# MP257_14x14.net
KiCad netlist of a schematic drawn in Altium Designer
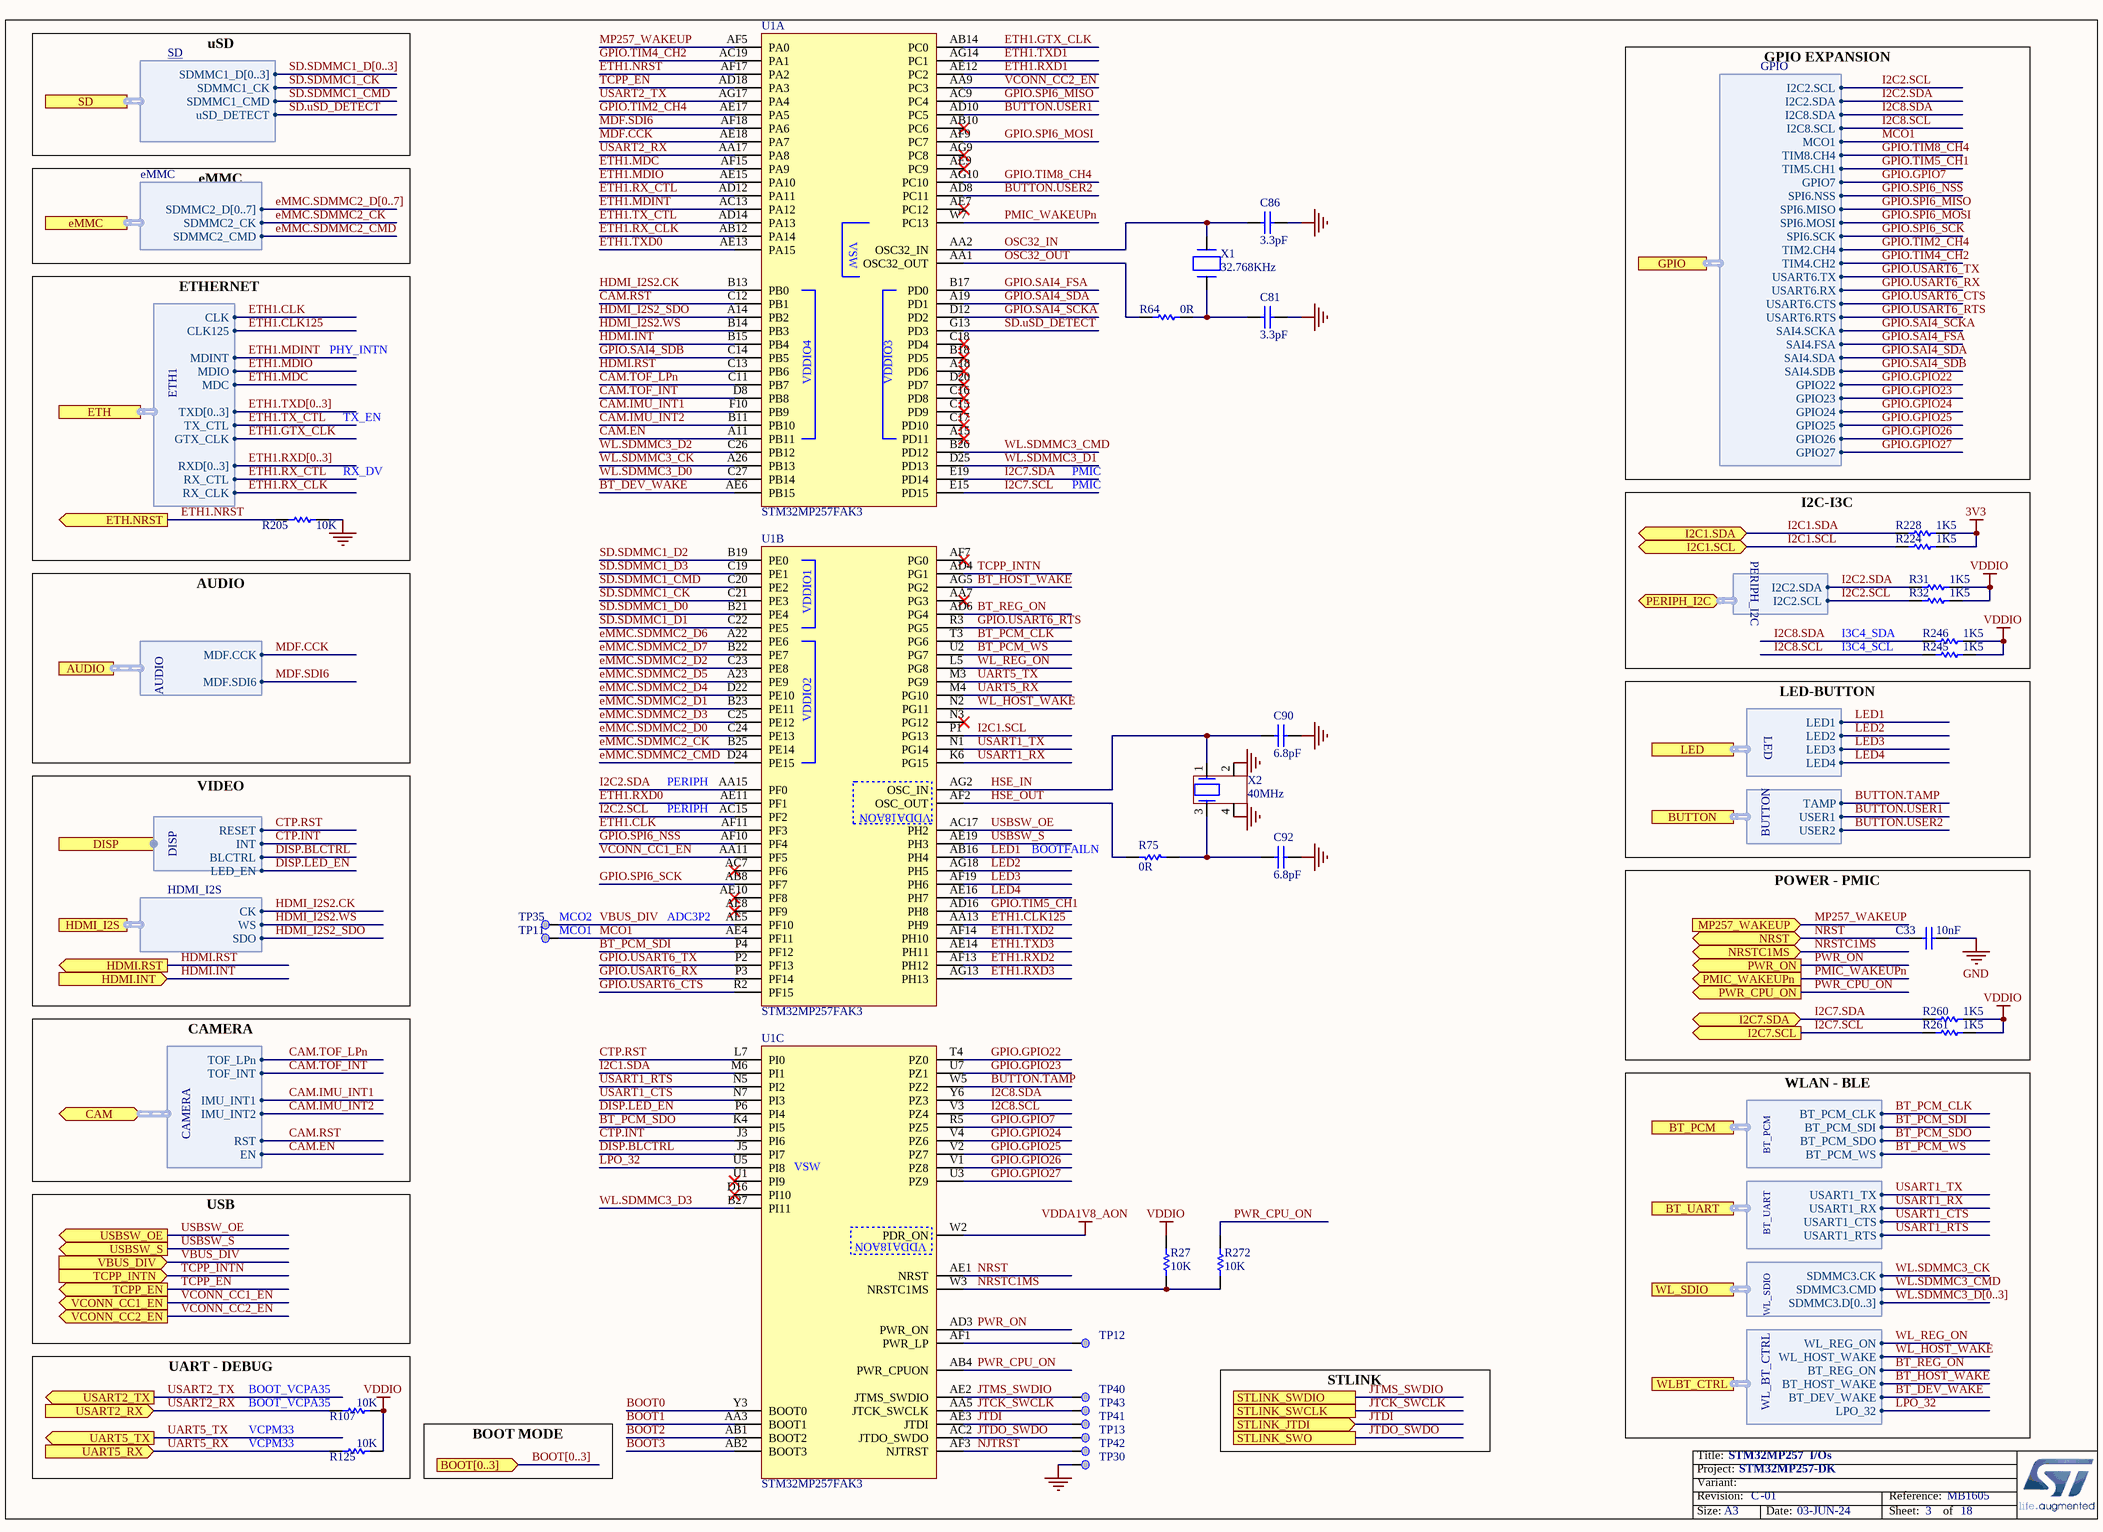
[diagram p0: MP257_14x14.SchDoc]

(export (version "E")
  (design (tool "Eeschema 10.0.6"))
  (components
    (comp (ref "C33")
      (value "10nF")
      (footprint "C0402")
      (description "Capacitor, MLCC, 10nF, 16V, X7R, 10%, 0402, T=0.5mm")
      (fields
        (field (name "INTERNAL_PART_NUMBER") "MCD-00011")
        (field (name "MANUFACTURER_PART_NUMBER") "CC0402KRX7R7BB103")
        (field (name "PROVIDED_BY") "SUBCO")
      )
      (libsource (lib "MCD_PARTS_database") (part "Capacitor"))
    )
    (comp (ref "C81")
      (value "3.3pF")
      (footprint "C0402")
      (description "Capacitor, MLCC, 3.3pF, 50V, NPO, +/-0.1pF, 0402, T=0.5mm")
      (fields (field (name "INTERNAL_PART_NUMBER") "MCD-01775") (field (name "MANUFACTURER") "YAGEO"))
      (libsource (lib "MCD_PARTS_database") (part "Capacitor"))
    )
    (comp (ref "C86")
      (value "3.3pF")
      (footprint "C0402")
      (description "Capacitor, MLCC, 3.3pF, 50V, NPO, +/-0.1pF, 0402, T=0.5mm")
      (fields (field (name "INTERNAL_PART_NUMBER") "MCD-01775") (field (name "MANUFACTURER") "YAGEO"))
      (libsource (lib "MCD_PARTS_database") (part "Capacitor"))
    )
    (comp (ref "C90")
      (value "6.8pF")
      (footprint "C0402")
      (description "Capacitor, MLCC, 6.8pF, 50V, NPO, +-0.25pF, 0402, T=0.5mm")
      (fields
        (field (name "INTERNAL_PART_NUMBER") "MCD-00674")
        (field (name "MANUFACTURER_PART_NUMBER") "CC0402CRNPO9BN6R8")
        (field (name "PROVIDED_BY") "SUBCO")
      )
      (libsource (lib "MCD_PARTS_database") (part "Capacitor"))
    )
    (comp (ref "C92")
      (value "6.8pF")
      (footprint "C0402")
      (description "Capacitor, MLCC, 6.8pF, 50V, NPO, +-0.25pF, 0402, T=0.5mm")
      (fields
        (field (name "INTERNAL_PART_NUMBER") "MCD-00674")
        (field (name "MANUFACTURER_PART_NUMBER") "CC0402CRNPO9BN6R8")
        (field (name "PROVIDED_BY") "SUBCO")
      )
      (libsource (lib "MCD_PARTS_database") (part "Capacitor"))
    )
    (comp (ref "R27")
      (value "10K")
      (footprint "R0402")
      (description "Resistor,10K,0402,1%,1/16W")
      (fields (field (name "INTERNAL_PART_NUMBER") "MCD-00053") (field (name "BMS_PART_NUMBER") "9131590"))
      (libsource (lib "MCD_PARTS_database") (part "Resistor"))
    )
    (comp (ref "R31")
      (value "1K5")
      (footprint "R0402")
      (description "Resistor,1K5,0402,1%,1/16W")
      (fields (field (name "INTERNAL_PART_NUMBER") "MCD-00068") (field (name "MANUFACTURER") "YAGEO"))
      (libsource (lib "MCD_PARTS_database") (part "Resistor"))
    )
    (comp (ref "R32")
      (value "1K5")
      (footprint "R0402")
      (description "Resistor,1K5,0402,1%,1/16W")
      (fields (field (name "INTERNAL_PART_NUMBER") "MCD-00068") (field (name "MANUFACTURER") "YAGEO"))
      (libsource (lib "MCD_PARTS_database") (part "Resistor"))
    )
    (comp (ref "R64")
      (value "0R")
      (footprint "R0402")
      (description "Resistor,0R,0402,5%,1/16W")
      (fields
        (field (name "INTERNAL_PART_NUMBER") "MCD-00052")
        (field (name "MANUFACTURER_PART_NUMBER") "RC0402JR-070RL")
        (field (name "PROVIDED_BY") "SUBCO")
      )
      (libsource (lib "MCD_PARTS_database") (part "Resistor"))
    )
    (comp (ref "R75")
      (value "0R")
      (footprint "R0402")
      (description "Resistor,0R,0402,5%,1/16W")
      (fields
        (field (name "INTERNAL_PART_NUMBER") "MCD-00052")
        (field (name "MANUFACTURER_PART_NUMBER") "RC0402JR-070RL")
        (field (name "PROVIDED_BY") "SUBCO")
      )
      (libsource (lib "MCD_PARTS_database") (part "Resistor"))
    )
    (comp (ref "R107")
      (value "10K")
      (footprint "R0402")
      (description "Resistor,10K,0402,1%,1/16W")
      (fields (field (name "INTERNAL_PART_NUMBER") "MCD-00053") (field (name "BMS_PART_NUMBER") "9131590"))
      (libsource (lib "MCD_PARTS_database") (part "Resistor"))
    )
    (comp (ref "R125")
      (value "10K")
      (footprint "R0402")
      (description "Resistor,10K,0402,1%,1/16W")
      (fields (field (name "INTERNAL_PART_NUMBER") "MCD-00053") (field (name "BMS_PART_NUMBER") "9131590"))
      (libsource (lib "MCD_PARTS_database") (part "Resistor"))
    )
    (comp (ref "R205")
      (value "10K")
      (footprint "R0402")
      (description "Resistor,10K,0402,1%,1/16W")
      (fields
        (field (name "INTERNAL_PART_NUMBER") "MCD-00053")
        (field (name "MANUFACTURER_PART_NUMBER") "RC0402FR-0710KL")
      )
      (libsource (lib "MCD_PARTS_database") (part "Resistor"))
    )
    (comp (ref "R224")
      (value "1K5")
      (footprint "R0402")
      (description "Resistor,1K5,0402,1%,1/16W")
      (fields (field (name "INTERNAL_PART_NUMBER") "MCD-00068") (field (name "MANUFACTURER") "YAGEO"))
      (libsource (lib "MCD_PARTS_database") (part "Resistor"))
    )
    (comp (ref "R228")
      (value "1K5")
      (footprint "R0402")
      (description "Resistor,1K5,0402,1%,1/16W")
      (fields (field (name "INTERNAL_PART_NUMBER") "MCD-00068") (field (name "MANUFACTURER") "YAGEO"))
      (libsource (lib "MCD_PARTS_database") (part "Resistor"))
    )
    (comp (ref "R245")
      (value "1K5")
      (footprint "R0402")
      (description "Resistor,1K5,0402,1%,1/16W")
      (fields (field (name "INTERNAL_PART_NUMBER") "MCD-00068") (field (name "MANUFACTURER") "YAGEO"))
      (libsource (lib "MCD_PARTS_database") (part "Resistor"))
    )
    (comp (ref "R246")
      (value "1K5")
      (footprint "R0402")
      (description "Resistor,1K5,0402,1%,1/16W")
      (fields (field (name "INTERNAL_PART_NUMBER") "MCD-00068") (field (name "MANUFACTURER") "YAGEO"))
      (libsource (lib "MCD_PARTS_database") (part "Resistor"))
    )
    (comp (ref "R260")
      (value "1K5")
      (footprint "R0402")
      (description "Resistor,1K5,0402,1%,1/16W")
      (fields (field (name "INTERNAL_PART_NUMBER") "MCD-00068") (field (name "MANUFACTURER") "YAGEO"))
      (libsource (lib "MCD_PARTS_database") (part "Resistor"))
    )
    (comp (ref "R261")
      (value "1K5")
      (footprint "R0402")
      (description "Resistor,1K5,0402,1%,1/16W")
      (fields (field (name "INTERNAL_PART_NUMBER") "MCD-00068") (field (name "MANUFACTURER") "YAGEO"))
      (libsource (lib "MCD_PARTS_database") (part "Resistor"))
    )
    (comp (ref "R272")
      (value "10K")
      (footprint "R0402")
      (description "Resistor,10K,0402,1%,1/16W")
      (fields (field (name "INTERNAL_PART_NUMBER") "MCD-00053") (field (name "BMS_PART_NUMBER") "9131590"))
      (libsource (lib "MCD_PARTS_database") (part "Resistor"))
    )
    (comp (ref "TP11")
      (value "Test Point")
      (footprint "TP_SMD_1MM")
      (description "Test Point 1mm")
      (fields
        (field (name "INTERNAL_PART_NUMBER") "MCD-00074")
        (field (name "MANUFACTURER_PART_NUMBER") "n/a")
      )
      (libsource (lib "") (part "Test Point_1"))
    )
    (comp (ref "TP12")
      (value "Test Point")
      (footprint "TP_SMD_1MM")
      (description "Test Point 1mm")
      (fields
        (field (name "INTERNAL_PART_NUMBER") "MCD-00074")
        (field (name "MANUFACTURER_PART_NUMBER") "n/a")
      )
      (libsource (lib "MCD_PARTS_database") (part "Test Point"))
    )
    (comp (ref "TP13")
      (value "Test Point")
      (footprint "TP_SMD_1MM")
      (description "Test Point 1mm")
      (fields
        (field (name "INTERNAL_PART_NUMBER") "MCD-00074")
        (field (name "MANUFACTURER_PART_NUMBER") "n/a")
      )
      (libsource (lib "MCD_PARTS_database") (part "Test Point"))
    )
    (comp (ref "TP30")
      (value "Test Point")
      (footprint "TP_SMD_1MM")
      (description "Test Point 1mm")
      (fields
        (field (name "INTERNAL_PART_NUMBER") "MCD-00074")
        (field (name "MANUFACTURER_PART_NUMBER") "n/a")
      )
      (libsource (lib "MCD_PARTS_database") (part "Test Point"))
    )
    (comp (ref "TP35")
      (value "Test Point")
      (footprint "TP_SMD_1MM")
      (description "Test Point 1mm")
      (fields
        (field (name "INTERNAL_PART_NUMBER") "MCD-00074")
        (field (name "MANUFACTURER_PART_NUMBER") "n/a")
      )
      (libsource (lib "") (part "Test Point_1"))
    )
    (comp (ref "TP40")
      (value "Test Point")
      (footprint "TP_SMD_1MM")
      (description "Test Point 1mm")
      (fields
        (field (name "INTERNAL_PART_NUMBER") "MCD-00074")
        (field (name "MANUFACTURER_PART_NUMBER") "n/a")
      )
      (libsource (lib "MCD_PARTS_database") (part "Test Point"))
    )
    (comp (ref "TP41")
      (value "Test Point")
      (footprint "TP_SMD_1MM")
      (description "Test Point 1mm")
      (fields
        (field (name "INTERNAL_PART_NUMBER") "MCD-00074")
        (field (name "MANUFACTURER_PART_NUMBER") "n/a")
      )
      (libsource (lib "MCD_PARTS_database") (part "Test Point"))
    )
    (comp (ref "TP42")
      (value "Test Point")
      (footprint "TP_SMD_1MM")
      (description "Test Point 1mm")
      (fields
        (field (name "INTERNAL_PART_NUMBER") "MCD-00074")
        (field (name "MANUFACTURER_PART_NUMBER") "n/a")
      )
      (libsource (lib "MCD_PARTS_database") (part "Test Point"))
    )
    (comp (ref "TP43")
      (value "Test Point")
      (footprint "TP_SMD_1MM")
      (description "Test Point 1mm")
      (fields
        (field (name "INTERNAL_PART_NUMBER") "MCD-00074")
        (field (name "MANUFACTURER_PART_NUMBER") "n/a")
      )
      (libsource (lib "MCD_PARTS_database") (part "Test Point"))
    )
    (comp (ref "U1")
      (value "STM32MP257FAK3")
      (footprint "ICC_TFBGA424_14X14_P050_H1P20_CODE-B0A2")
      (description "MPU , 2xCortex-A35@1.5GHz, Cortex-M33@400MHz, TFBGA 14x14, pitch 0.5, 648KB SRAM, With Crypto")
      (fields
        (field (name "INTERNAL_PART_NUMBER") "MCD-03375")
        (field (name "MANUFACTURER") "STMICROELECTRONICS")
      )
      (libsource (lib "MCD_PARTS_database") (part "STM32MP257FAK3"))
    )
    (comp (ref "X1")
      (value "32.768KHz")
      (footprint "CRY_NX2012SA_2P")
      (description "Crystal, 32.768kHz, 6pF, +/-20ppm, 80K, 2.05x1.2mm")
      (fields (field (name "INTERNAL_PART_NUMBER") "MCD-01479") (field (name "BMS_PART_NUMBER") "9157049"))
      (libsource (lib "MCD_PARTS_database") (part "XTAL_2_PINS"))
    )
    (comp (ref "X2")
      (value "40MHz")
      (footprint "CRY_NX1612SA_4P")
      (description "Crystal, 40MHz, 6pF, +/-20ppm, 80R, 1.6x1.2mm")
      (fields (field (name "INTERNAL_PART_NUMBER") "MCD-02344") (field (name "MANUFACTURER") "NDK"))
      (libsource (lib "MCD_PARTS_database") (part "XTAL_4_PINS"))
    )
  )
  (nets
    (net (code "17") (name "/BOOT0") (class "Default")
      (node (ref "U1") (pin "Y3") (pinfunction "BOOT0_Y3") (pintype "passive"))
    )
    (net (code "18") (name "/BOOT1") (class "Default")
      (node (ref "U1") (pin "AA3") (pinfunction "BOOT1_AA3") (pintype "passive"))
    )
    (net (code "19") (name "/BOOT2") (class "Default")
      (node (ref "U1") (pin "AB1") (pinfunction "BOOT2_AB1") (pintype "passive"))
    )
    (net (code "20") (name "/BOOT3") (class "Default")
      (node (ref "U1") (pin "AB2") (pinfunction "BOOT3_AB2") (pintype "passive"))
    )
    (net (code "22") (name "/BT_DEV_WAKE") (class "Default")
      (node (ref "U1") (pin "AE6") (pinfunction "PB15_AE6") (pintype "passive"))
    )
    (net (code "23") (name "/BT_HOST_WAKE") (class "Default")
      (node (ref "U1") (pin "AG5") (pinfunction "PG2_AG5") (pintype "passive"))
    )
    (net (code "24") (name "/BT_PCM_CLK") (class "Default")
      (node (ref "U1") (pin "T3") (pinfunction "PG6_T3") (pintype "passive"))
    )
    (net (code "25") (name "/BT_PCM_SDI") (class "Default")
      (node (ref "U1") (pin "P4") (pinfunction "PF12_P4") (pintype "passive"))
    )
    (net (code "26") (name "/BT_PCM_SDO") (class "Default")
      (node (ref "U1") (pin "K4") (pinfunction "PI5_K4") (pintype "passive"))
    )
    (net (code "27") (name "/BT_PCM_WS") (class "Default")
      (node (ref "U1") (pin "U2") (pinfunction "PG7_U2") (pintype "passive"))
    )
    (net (code "28") (name "/BT_REG_ON") (class "Default")
      (node (ref "U1") (pin "AD6") (pinfunction "PG4_AD6") (pintype "passive"))
    )
    (net (code "29") (name "/BUTTON.TAMP") (class "Default")
      (node (ref "U1") (pin "W5") (pinfunction "PZ2_W5") (pintype "passive"))
    )
    (net (code "30") (name "/BUTTON.USER1") (class "Default")
      (node (ref "U1") (pin "AD10") (pinfunction "PC5_AD10") (pintype "passive"))
    )
    (net (code "31") (name "/BUTTON.USER2") (class "Default")
      (node (ref "U1") (pin "AD8") (pinfunction "PC11_AD8") (pintype "passive"))
    )
    (net (code "32") (name "/CAM.EN") (class "Default")
      (node (ref "U1") (pin "A11") (pinfunction "PB11_A11") (pintype "passive"))
    )
    (net (code "33") (name "/CAM.IMU_INT1") (class "Default")
      (node (ref "U1") (pin "F10") (pinfunction "PB9_F10") (pintype "passive"))
    )
    (net (code "34") (name "/CAM.IMU_INT2") (class "Default")
      (node (ref "U1") (pin "B11") (pinfunction "PB10_B11") (pintype "passive"))
    )
    (net (code "35") (name "/CAM.RST") (class "Default")
      (node (ref "U1") (pin "C12") (pinfunction "PB1_C12") (pintype "passive"))
    )
    (net (code "36") (name "/CAM.TOF_INT") (class "Default")
      (node (ref "U1") (pin "D8") (pinfunction "PB8_D8") (pintype "passive"))
    )
    (net (code "37") (name "/CAM.TOF_LPn") (class "Default")
      (node (ref "U1") (pin "C11") (pinfunction "PB7_C11") (pintype "passive"))
    )
    (net (code "38") (name "/CTP.INT") (class "Default")
      (node (ref "U1") (pin "J3") (pinfunction "PI6_J3") (pintype "passive"))
    )
    (net (code "39") (name "/CTP.RST") (class "Default")
      (node (ref "U1") (pin "L7") (pinfunction "PI0_L7") (pintype "passive"))
    )
    (net (code "40") (name "/DISP.BLCTRL") (class "Default")
      (node (ref "U1") (pin "J5") (pinfunction "PI7_J5") (pintype "passive"))
    )
    (net (code "41") (name "/DISP.LED_EN") (class "Default")
      (node (ref "U1") (pin "P6") (pinfunction "PI4_P6") (pintype "passive"))
    )
    (net (code "42") (name "/ETH1.CLK") (class "Default")
      (node (ref "U1") (pin "AF11") (pinfunction "PF3_AF11") (pintype "passive"))
    )
    (net (code "43") (name "/ETH1.CLK125") (class "Default")
      (node (ref "U1") (pin "AA13") (pinfunction "PH9_AA13") (pintype "passive"))
    )
    (net (code "44") (name "/ETH1.GTX_CLK") (class "Default")
      (node (ref "U1") (pin "AB14") (pinfunction "PC0_AB14") (pintype "passive"))
    )
    (net (code "45") (name "/ETH1.MDC") (class "Default")
      (node (ref "U1") (pin "AF15") (pinfunction "PA9_AF15") (pintype "passive"))
    )
    (net (code "46") (name "/ETH1.MDINT") (class "Default")
      (node (ref "U1") (pin "AC13") (pinfunction "PA12_AC13") (pintype "passive"))
    )
    (net (code "47") (name "/ETH1.MDIO") (class "Default")
      (node (ref "U1") (pin "AE15") (pinfunction "PA10_AE15") (pintype "passive"))
    )
    (net (code "48") (name "/ETH1.NRST") (class "Default")
      (node (ref "R205") (pin "1") (pinfunction "1_1") (pintype "passive"))
      (node (ref "U1") (pin "AF17") (pinfunction "PA2_AF17") (pintype "passive"))
    )
    (net (code "49") (name "/ETH1.RXD0") (class "Default")
      (node (ref "U1") (pin "AE11") (pinfunction "PF1_AE11") (pintype "passive"))
    )
    (net (code "50") (name "/ETH1.RXD1") (class "Default")
      (node (ref "U1") (pin "AE12") (pinfunction "PC2_AE12") (pintype "passive"))
    )
    (net (code "51") (name "/ETH1.RXD2") (class "Default")
      (node (ref "U1") (pin "AF13") (pinfunction "PH12_AF13") (pintype "passive"))
    )
    (net (code "52") (name "/ETH1.RXD3") (class "Default")
      (node (ref "U1") (pin "AG13") (pinfunction "PH13_AG13") (pintype "passive"))
    )
    (net (code "54") (name "/ETH1.RX_CLK") (class "Default")
      (node (ref "U1") (pin "AB12") (pinfunction "PA14_AB12") (pintype "passive"))
    )
    (net (code "55") (name "/ETH1.RX_CTL") (class "Default")
      (node (ref "U1") (pin "AD12") (pinfunction "PA11_AD12") (pintype "passive"))
    )
    (net (code "56") (name "/ETH1.TXD0") (class "Default")
      (node (ref "U1") (pin "AE13") (pinfunction "PA15_AE13") (pintype "passive"))
    )
    (net (code "57") (name "/ETH1.TXD1") (class "Default")
      (node (ref "U1") (pin "AG14") (pinfunction "PC1_AG14") (pintype "passive"))
    )
    (net (code "58") (name "/ETH1.TXD2") (class "Default")
      (node (ref "U1") (pin "AF14") (pinfunction "PH10_AF14") (pintype "passive"))
    )
    (net (code "59") (name "/ETH1.TXD3") (class "Default")
      (node (ref "U1") (pin "AE14") (pinfunction "PH11_AE14") (pintype "passive"))
    )
    (net (code "61") (name "/ETH1.TX_CTL") (class "Default")
      (node (ref "U1") (pin "AD14") (pinfunction "PA13_AD14") (pintype "passive"))
    )
    (net (code "62") (name "/GPIO.GPIO7") (class "Default")
      (node (ref "U1") (pin "R5") (pinfunction "PZ5_R5") (pintype "passive"))
    )
    (net (code "63") (name "/GPIO.GPIO22") (class "Default")
      (node (ref "U1") (pin "T4") (pinfunction "PZ0_T4") (pintype "passive"))
    )
    (net (code "64") (name "/GPIO.GPIO23") (class "Default")
      (node (ref "U1") (pin "U7") (pinfunction "PZ1_U7") (pintype "passive"))
    )
    (net (code "65") (name "/GPIO.GPIO24") (class "Default")
      (node (ref "U1") (pin "V4") (pinfunction "PZ6_V4") (pintype "passive"))
    )
    (net (code "66") (name "/GPIO.GPIO25") (class "Default")
      (node (ref "U1") (pin "V2") (pinfunction "PZ7_V2") (pintype "passive"))
    )
    (net (code "67") (name "/GPIO.GPIO26") (class "Default")
      (node (ref "U1") (pin "V1") (pinfunction "PZ8_V1") (pintype "passive"))
    )
    (net (code "68") (name "/GPIO.GPIO27") (class "Default")
      (node (ref "U1") (pin "U3") (pinfunction "PZ9_U3") (pintype "passive"))
    )
    (net (code "69") (name "/GPIO.SAI4_FSA") (class "Default")
      (node (ref "U1") (pin "B17") (pinfunction "PD0_B17") (pintype "passive"))
    )
    (net (code "70") (name "/GPIO.SAI4_SCKA") (class "Default")
      (node (ref "U1") (pin "D12") (pinfunction "PD2_D12") (pintype "passive"))
    )
    (net (code "71") (name "/GPIO.SAI4_SDA") (class "Default")
      (node (ref "U1") (pin "A19") (pinfunction "PD1_A19") (pintype "passive"))
    )
    (net (code "72") (name "/GPIO.SAI4_SDB") (class "Default")
      (node (ref "U1") (pin "C14") (pinfunction "PB5_C14") (pintype "passive"))
    )
    (net (code "73") (name "/GPIO.SPI6_MISO") (class "Default")
      (node (ref "U1") (pin "AC9") (pinfunction "PC4_AC9") (pintype "passive"))
    )
    (net (code "74") (name "/GPIO.SPI6_MOSI") (class "Default")
      (node (ref "U1") (pin "AF9") (pinfunction "PC7_AF9") (pintype "passive"))
    )
    (net (code "75") (name "/GPIO.SPI6_NSS") (class "Default")
      (node (ref "U1") (pin "AF10") (pinfunction "PF4_AF10") (pintype "passive"))
    )
    (net (code "76") (name "/GPIO.SPI6_SCK") (class "Default")
      (node (ref "U1") (pin "AB8") (pinfunction "PF7_AB8") (pintype "passive"))
    )
    (net (code "77") (name "/GPIO.TIM2_CH4") (class "Default")
      (node (ref "U1") (pin "AE17") (pinfunction "PA5_AE17") (pintype "passive"))
    )
    (net (code "78") (name "/GPIO.TIM4_CH2") (class "Default")
      (node (ref "U1") (pin "AC19") (pinfunction "PA1_AC19") (pintype "passive"))
    )
    (net (code "79") (name "/GPIO.TIM5_CH1") (class "Default")
      (node (ref "U1") (pin "AD16") (pinfunction "PH8_AD16") (pintype "passive"))
    )
    (net (code "80") (name "/GPIO.TIM8_CH4") (class "Default")
      (node (ref "U1") (pin "AG10") (pinfunction "PC10_AG10") (pintype "passive"))
    )
    (net (code "81") (name "/GPIO.USART6_CTS") (class "Default")
      (node (ref "U1") (pin "R2") (pinfunction "PF15_R2") (pintype "passive"))
    )
    (net (code "82") (name "/GPIO.USART6_RTS") (class "Default")
      (node (ref "U1") (pin "R3") (pinfunction "PG5_R3") (pintype "passive"))
    )
    (net (code "83") (name "/GPIO.USART6_RX") (class "Default")
      (node (ref "U1") (pin "P3") (pinfunction "PF14_P3") (pintype "passive"))
    )
    (net (code "84") (name "/GPIO.USART6_TX") (class "Default")
      (node (ref "U1") (pin "P2") (pinfunction "PF13_P2") (pintype "passive"))
    )
    (net (code "85") (name "/HDMI.INT") (class "Default")
      (node (ref "U1") (pin "B15") (pinfunction "PB4_B15") (pintype "passive"))
    )
    (net (code "86") (name "/HDMI.RST") (class "Default")
      (node (ref "U1") (pin "C13") (pinfunction "PB6_C13") (pintype "passive"))
    )
    (net (code "87") (name "/HDMI_I2S2.CK") (class "Default")
      (node (ref "U1") (pin "B13") (pinfunction "PB0_B13") (pintype "passive"))
    )
    (net (code "88") (name "/HDMI_I2S2.WS") (class "Default")
      (node (ref "U1") (pin "B14") (pinfunction "PB3_B14") (pintype "passive"))
    )
    (net (code "89") (name "/HDMI_I2S2_SDO") (class "Default")
      (node (ref "U1") (pin "A14") (pinfunction "PB2_A14") (pintype "passive"))
    )
    (net (code "90") (name "/HSE_IN") (class "Default")
      (node (ref "C90") (pin "2") (pinfunction "2_2") (pintype "passive"))
      (node (ref "U1") (pin "AG2") (pinfunction "OSC_IN_AG2") (pintype "passive"))
      (node (ref "X2") (pin "1") (pinfunction "1_1") (pintype "passive"))
    )
    (net (code "91") (name "/HSE_OUT") (class "Default")
      (node (ref "R75") (pin "2") (pinfunction "2_2") (pintype "passive"))
      (node (ref "U1") (pin "AF2") (pinfunction "OSC_OUT_AF2") (pintype "passive"))
    )
    (net (code "92") (name "/I2C1.SCL") (class "Default")
      (node (ref "R224") (pin "1") (pinfunction "1_1") (pintype "passive"))
      (node (ref "U1") (pin "P1") (pinfunction "PG13_P1") (pintype "passive"))
    )
    (net (code "93") (name "/I2C1.SDA") (class "Default")
      (node (ref "R228") (pin "1") (pinfunction "1_1") (pintype "passive"))
      (node (ref "U1") (pin "M6") (pinfunction "PI1_M6") (pintype "passive"))
    )
    (net (code "94") (name "/I2C2.SCL") (class "Default")
      (node (ref "R32") (pin "1") (pinfunction "1_1") (pintype "passive"))
      (node (ref "U1") (pin "AC15") (pinfunction "PF2_AC15") (pintype "passive"))
    )
    (net (code "95") (name "/I2C2.SDA") (class "Default")
      (node (ref "R31") (pin "1") (pinfunction "1_1") (pintype "passive"))
      (node (ref "U1") (pin "AA15") (pinfunction "PF0_AA15") (pintype "passive"))
    )
    (net (code "96") (name "/I2C7.SCL") (class "Default")
      (node (ref "R261") (pin "1") (pinfunction "1_1") (pintype "passive"))
      (node (ref "U1") (pin "E15") (pinfunction "PD15_E15") (pintype "passive"))
    )
    (net (code "97") (name "/I2C7.SDA") (class "Default")
      (node (ref "R260") (pin "1") (pinfunction "1_1") (pintype "passive"))
      (node (ref "U1") (pin "E19") (pinfunction "PD14_E19") (pintype "passive"))
    )
    (net (code "98") (name "/I2C8.SCL") (class "Default")
      (node (ref "R245") (pin "1") (pinfunction "1_1") (pintype "passive"))
      (node (ref "U1") (pin "V3") (pinfunction "PZ4_V3") (pintype "passive"))
    )
    (net (code "99") (name "/I2C8.SDA") (class "Default")
      (node (ref "R246") (pin "1") (pinfunction "1_1") (pintype "passive"))
      (node (ref "U1") (pin "Y6") (pinfunction "PZ3_Y6") (pintype "passive"))
    )
    (net (code "100") (name "/JTCK_SWCLK") (class "Default")
      (node (ref "TP43") (pin "1") (pinfunction "1_1") (pintype "passive"))
      (node (ref "U1") (pin "AA5") (pinfunction "JTCK_SWCLK_AA5") (pintype "passive"))
    )
    (net (code "101") (name "/JTDI") (class "Default")
      (node (ref "TP41") (pin "1") (pinfunction "1_1") (pintype "passive"))
      (node (ref "U1") (pin "AE3") (pinfunction "JTDI_AE3") (pintype "passive"))
    )
    (net (code "102") (name "/JTDO_SWDO") (class "Default")
      (node (ref "TP13") (pin "1") (pinfunction "1_1") (pintype "passive"))
      (node (ref "U1") (pin "AC2") (pinfunction "JTDO_SWDO_AC2") (pintype "passive"))
    )
    (net (code "103") (name "/JTMS_SWDIO") (class "Default")
      (node (ref "TP40") (pin "1") (pinfunction "1_1") (pintype "passive"))
      (node (ref "U1") (pin "AE2") (pinfunction "JTMS_SWDIO_AE2") (pintype "passive"))
    )
    (net (code "104") (name "/LED1") (class "Default")
      (node (ref "U1") (pin "AB16") (pinfunction "PH4_AB16") (pintype "passive"))
    )
    (net (code "105") (name "/LED2") (class "Default")
      (node (ref "U1") (pin "AG18") (pinfunction "PH5_AG18") (pintype "passive"))
    )
    (net (code "106") (name "/LED3") (class "Default")
      (node (ref "U1") (pin "AF19") (pinfunction "PH6_AF19") (pintype "passive"))
    )
    (net (code "107") (name "/LED4") (class "Default")
      (node (ref "U1") (pin "AE16") (pinfunction "PH7_AE16") (pintype "passive"))
    )
    (net (code "108") (name "/LPO_32") (class "Default")
      (node (ref "U1") (pin "U5") (pinfunction "PI8_U5") (pintype "passive"))
    )
    (net (code "109") (name "/MCO1") (class "Default")
      (node (ref "TP11") (pin "1") (pinfunction "1_1") (pintype "passive"))
      (node (ref "U1") (pin "AE4") (pinfunction "PF11_AE4") (pintype "passive"))
    )
    (net (code "110") (name "/MDF.CCK") (class "Default")
      (node (ref "U1") (pin "AE18") (pinfunction "PA7_AE18") (pintype "passive"))
    )
    (net (code "111") (name "/MDF.SDI6") (class "Default")
      (node (ref "U1") (pin "AF18") (pinfunction "PA6_AF18") (pintype "passive"))
    )
    (net (code "112") (name "/MP257_WAKEUP") (class "Default")
      (node (ref "U1") (pin "AF5") (pinfunction "PA0_AF5") (pintype "passive"))
    )
    (net (code "113") (name "/NJTRST") (class "Default")
      (node (ref "TP42") (pin "1") (pinfunction "1_1") (pintype "passive"))
      (node (ref "U1") (pin "AF3") (pinfunction "NJTRST_AF3") (pintype "passive"))
    )
    (net (code "114") (name "/NRST") (class "Default")
      (node (ref "C33") (pin "2") (pinfunction "2_2") (pintype "passive"))
      (node (ref "U1") (pin "AE1") (pinfunction "NRST_AE1") (pintype "passive"))
    )
    (net (code "115") (name "/NRSTC1MS") (class "Default")
      (node (ref "R27") (pin "1") (pinfunction "1_1") (pintype "passive"))
      (node (ref "R272") (pin "1") (pinfunction "1_1") (pintype "passive"))
      (node (ref "U1") (pin "W3") (pinfunction "NRSTC1MS_W3") (pintype "passive"))
    )
    (net (code "116") (name "/OSC32_IN") (class "Default")
      (node (ref "C86") (pin "1") (pinfunction "1_1") (pintype "passive"))
      (node (ref "U1") (pin "AA2") (pinfunction "OSC32_IN_AA2") (pintype "passive"))
      (node (ref "X1") (pin "2") (pinfunction "X2_2") (pintype "passive"))
    )
    (net (code "117") (name "/OSC32_OUT") (class "Default")
      (node (ref "R64") (pin "1") (pinfunction "1_1") (pintype "passive"))
      (node (ref "U1") (pin "AA1") (pinfunction "OSC32_OUT_AA1") (pintype "passive"))
    )
    (net (code "118") (name "/PMIC_WAKEUPn") (class "Default")
      (node (ref "U1") (pin "W7") (pinfunction "PC13_W7") (pintype "passive"))
    )
    (net (code "119") (name "/PWR_CPU_ON") (class "Default")
      (node (ref "R272") (pin "2") (pinfunction "2_2") (pintype "passive"))
      (node (ref "U1") (pin "AB4") (pinfunction "PWR_CPUON_AB4") (pintype "passive"))
    )
    (net (code "120") (name "/PWR_ON") (class "Default")
      (node (ref "U1") (pin "AD3") (pinfunction "PWR_ON_AD3") (pintype "passive"))
    )
    (net (code "121") (name "/SD.SDMMC1_CK") (class "Default")
      (node (ref "U1") (pin "C21") (pinfunction "PE3_C21") (pintype "passive"))
    )
    (net (code "122") (name "/SD.SDMMC1_CMD") (class "Default")
      (node (ref "U1") (pin "C20") (pinfunction "PE2_C20") (pintype "passive"))
    )
    (net (code "123") (name "/SD.SDMMC1_D0") (class "Default")
      (node (ref "U1") (pin "B21") (pinfunction "PE4_B21") (pintype "passive"))
    )
    (net (code "124") (name "/SD.SDMMC1_D1") (class "Default")
      (node (ref "U1") (pin "C22") (pinfunction "PE5_C22") (pintype "passive"))
    )
    (net (code "125") (name "/SD.SDMMC1_D2") (class "Default")
      (node (ref "U1") (pin "B19") (pinfunction "PE0_B19") (pintype "passive"))
    )
    (net (code "126") (name "/SD.SDMMC1_D3") (class "Default")
      (node (ref "U1") (pin "C19") (pinfunction "PE1_C19") (pintype "passive"))
    )
    (net (code "128") (name "/SD.uSD_DETECT") (class "Default")
      (node (ref "U1") (pin "G13") (pinfunction "PD3_G13") (pintype "passive"))
    )
    (net (code "129") (name "/TCPP_EN") (class "Default")
      (node (ref "U1") (pin "AD18") (pinfunction "PA3_AD18") (pintype "passive"))
    )
    (net (code "130") (name "/TCPP_INTN") (class "Default")
      (node (ref "U1") (pin "AD4") (pinfunction "PG1_AD4") (pintype "passive"))
    )
    (net (code "131") (name "/UART5_RX") (class "Default")
      (node (ref "R125") (pin "1") (pinfunction "1_1") (pintype "passive"))
      (node (ref "U1") (pin "M4") (pinfunction "PG10_M4") (pintype "passive"))
    )
    (net (code "132") (name "/UART5_TX") (class "Default")
      (node (ref "U1") (pin "M3") (pinfunction "PG9_M3") (pintype "passive"))
    )
    (net (code "133") (name "/USART1_CTS") (class "Default")
      (node (ref "U1") (pin "N7") (pinfunction "PI3_N7") (pintype "passive"))
    )
    (net (code "134") (name "/USART1_RTS") (class "Default")
      (node (ref "U1") (pin "N5") (pinfunction "PI2_N5") (pintype "passive"))
    )
    (net (code "135") (name "/USART1_RX") (class "Default")
      (node (ref "U1") (pin "K6") (pinfunction "PG15_K6") (pintype "passive"))
    )
    (net (code "136") (name "/USART1_TX") (class "Default")
      (node (ref "U1") (pin "N1") (pinfunction "PG14_N1") (pintype "passive"))
    )
    (net (code "137") (name "/USART2_RX") (class "Default")
      (node (ref "R107") (pin "1") (pinfunction "1_1") (pintype "passive"))
      (node (ref "U1") (pin "AA17") (pinfunction "PA8_AA17") (pintype "passive"))
    )
    (net (code "138") (name "/USART2_TX") (class "Default")
      (node (ref "U1") (pin "AG17") (pinfunction "PA4_AG17") (pintype "passive"))
    )
    (net (code "139") (name "/USBSW_OE") (class "Default")
      (node (ref "U1") (pin "AC17") (pinfunction "PH2_AC17") (pintype "passive"))
    )
    (net (code "140") (name "/USBSW_S") (class "Default")
      (node (ref "U1") (pin "AE19") (pinfunction "PH3_AE19") (pintype "passive"))
    )
    (net (code "141") (name "/VBUS_DIV") (class "Default")
      (node (ref "TP35") (pin "1") (pinfunction "1_1") (pintype "passive"))
      (node (ref "U1") (pin "AE5") (pinfunction "PF10_AE5") (pintype "passive"))
    )
    (net (code "142") (name "/VCONN_CC1_EN") (class "Default")
      (node (ref "U1") (pin "AA11") (pinfunction "PF5_AA11") (pintype "passive"))
    )
    (net (code "143") (name "/VCONN_CC2_EN") (class "Default")
      (node (ref "U1") (pin "AA9") (pinfunction "PC3_AA9") (pintype "passive"))
    )
    (net (code "144") (name "/WL.SDMMC3_CK") (class "Default")
      (node (ref "U1") (pin "A26") (pinfunction "PB13_A26") (pintype "passive"))
    )
    (net (code "145") (name "/WL.SDMMC3_CMD") (class "Default")
      (node (ref "U1") (pin "B26") (pinfunction "PD12_B26") (pintype "passive"))
    )
    (net (code "146") (name "/WL.SDMMC3_D0") (class "Default")
      (node (ref "U1") (pin "C27") (pinfunction "PB14_C27") (pintype "passive"))
    )
    (net (code "147") (name "/WL.SDMMC3_D1") (class "Default")
      (node (ref "U1") (pin "D25") (pinfunction "PD13_D25") (pintype "passive"))
    )
    (net (code "148") (name "/WL.SDMMC3_D2") (class "Default")
      (node (ref "U1") (pin "C26") (pinfunction "PB12_C26") (pintype "passive"))
    )
    (net (code "149") (name "/WL.SDMMC3_D3") (class "Default")
      (node (ref "U1") (pin "B27") (pinfunction "PI11_B27") (pintype "passive"))
    )
    (net (code "150") (name "/WL_HOST_WAKE") (class "Default")
      (node (ref "U1") (pin "N2") (pinfunction "PG11_N2") (pintype "passive"))
    )
    (net (code "151") (name "/WL_REG_ON") (class "Default")
      (node (ref "U1") (pin "L5") (pinfunction "PG8_L5") (pintype "passive"))
    )
    (net (code "153") (name "/eMMC.SDMMC2_CK") (class "Default")
      (node (ref "U1") (pin "B25") (pinfunction "PE14_B25") (pintype "passive"))
    )
    (net (code "154") (name "/eMMC.SDMMC2_CMD") (class "Default")
      (node (ref "U1") (pin "D24") (pinfunction "PE15_D24") (pintype "passive"))
    )
    (net (code "155") (name "/eMMC.SDMMC2_D0") (class "Default")
      (node (ref "U1") (pin "C24") (pinfunction "PE13_C24") (pintype "passive"))
    )
    (net (code "156") (name "/eMMC.SDMMC2_D1") (class "Default")
      (node (ref "U1") (pin "B23") (pinfunction "PE11_B23") (pintype "passive"))
    )
    (net (code "157") (name "/eMMC.SDMMC2_D2") (class "Default")
      (node (ref "U1") (pin "C23") (pinfunction "PE8_C23") (pintype "passive"))
    )
    (net (code "158") (name "/eMMC.SDMMC2_D3") (class "Default")
      (node (ref "U1") (pin "C25") (pinfunction "PE12_C25") (pintype "passive"))
    )
    (net (code "159") (name "/eMMC.SDMMC2_D4") (class "Default")
      (node (ref "U1") (pin "D22") (pinfunction "PE10_D22") (pintype "passive"))
    )
    (net (code "160") (name "/eMMC.SDMMC2_D5") (class "Default")
      (node (ref "U1") (pin "A23") (pinfunction "PE9_A23") (pintype "passive"))
    )
    (net (code "161") (name "/eMMC.SDMMC2_D6") (class "Default")
      (node (ref "U1") (pin "A22") (pinfunction "PE6_A22") (pintype "passive"))
    )
    (net (code "162") (name "/eMMC.SDMMC2_D7") (class "Default")
      (node (ref "U1") (pin "B22") (pinfunction "PE7_B22") (pintype "passive"))
    )
    (net (code "179") (name "3V3") (class "Default")
      (node (ref "R224") (pin "2") (pinfunction "2_2") (pintype "passive"))
      (node (ref "R228") (pin "2") (pinfunction "2_2") (pintype "passive"))
    )
    (net (code "180") (name "GND") (class "Default")
      (node (ref "C33") (pin "1") (pinfunction "1_1") (pintype "passive"))
      (node (ref "C81") (pin "2") (pinfunction "2_2") (pintype "passive"))
      (node (ref "C86") (pin "2") (pinfunction "2_2") (pintype "passive"))
      (node (ref "C90") (pin "1") (pinfunction "1_1") (pintype "passive"))
      (node (ref "C92") (pin "2") (pinfunction "2_2") (pintype "passive"))
      (node (ref "R205") (pin "2") (pinfunction "2_2") (pintype "passive"))
      (node (ref "TP30") (pin "1") (pinfunction "1_1") (pintype "passive"))
      (node (ref "X2") (pin "2") (pinfunction "2_2") (pintype "passive"))
      (node (ref "X2") (pin "4") (pinfunction "4_4") (pintype "passive"))
    )
    (net (code "181") (name "Net-(C92-Pad1)") (class "Default")
      (node (ref "C92") (pin "1") (pinfunction "1_1") (pintype "passive"))
      (node (ref "R75") (pin "1") (pinfunction "1_1") (pintype "passive"))
      (node (ref "X2") (pin "3") (pinfunction "3_3") (pintype "passive"))
    )
    (net (code "182") (name "Net-(U1C-PWR_LP)") (class "Default")
      (node (ref "TP12") (pin "1") (pinfunction "1_1") (pintype "passive"))
      (node (ref "U1") (pin "AF1") (pinfunction "PWR_LP_AF1") (pintype "passive"))
    )
    (net (code "183") (name "Net-(X1-X1)") (class "Default")
      (node (ref "C81") (pin "1") (pinfunction "1_1") (pintype "passive"))
      (node (ref "R64") (pin "2") (pinfunction "2_2") (pintype "passive"))
      (node (ref "X1") (pin "1") (pinfunction "X1_1") (pintype "passive"))
    )
    (net (code "184") (name "VDDA1V8_AON") (class "Default")
      (node (ref "U1") (pin "W2") (pinfunction "PDR_ON_W2") (pintype "passive"))
    )
    (net (code "185") (name "VDDIO") (class "Default")
      (node (ref "R107") (pin "2") (pinfunction "2_2") (pintype "passive"))
      (node (ref "R125") (pin "2") (pinfunction "2_2") (pintype "passive"))
      (node (ref "R245") (pin "2") (pinfunction "2_2") (pintype "passive"))
      (node (ref "R246") (pin "2") (pinfunction "2_2") (pintype "passive"))
      (node (ref "R260") (pin "2") (pinfunction "2_2") (pintype "passive"))
      (node (ref "R261") (pin "2") (pinfunction "2_2") (pintype "passive"))
      (node (ref "R27") (pin "2") (pinfunction "2_2") (pintype "passive"))
      (node (ref "R31") (pin "2") (pinfunction "2_2") (pintype "passive"))
      (node (ref "R32") (pin "2") (pinfunction "2_2") (pintype "passive"))
    )
    (net (code "186") (name "unconnected-(U1A-PC6-PadAB10)") (class "Default")
      (node (ref "U1") (pin "AB10") (pinfunction "PC6_AB10") (pintype "passive+no_connect"))
    )
    (net (code "187") (name "unconnected-(U1A-PC8-PadAG9)") (class "Default")
      (node (ref "U1") (pin "AG9") (pinfunction "PC8_AG9") (pintype "passive+no_connect"))
    )
    (net (code "188") (name "unconnected-(U1A-PC9-PadAE9)") (class "Default")
      (node (ref "U1") (pin "AE9") (pinfunction "PC9_AE9") (pintype "passive+no_connect"))
    )
    (net (code "189") (name "unconnected-(U1A-PC12-PadAE7)") (class "Default")
      (node (ref "U1") (pin "AE7") (pinfunction "PC12_AE7") (pintype "passive+no_connect"))
    )
    (net (code "190") (name "unconnected-(U1A-PD4-PadC18)") (class "Default")
      (node (ref "U1") (pin "C18") (pinfunction "PD4_C18") (pintype "passive+no_connect"))
    )
    (net (code "191") (name "unconnected-(U1A-PD5-PadB18)") (class "Default")
      (node (ref "U1") (pin "B18") (pinfunction "PD5_B18") (pintype "passive+no_connect"))
    )
    (net (code "192") (name "unconnected-(U1A-PD6-PadA18)") (class "Default")
      (node (ref "U1") (pin "A18") (pinfunction "PD6_A18") (pintype "passive+no_connect"))
    )
    (net (code "193") (name "unconnected-(U1A-PD7-PadD20)") (class "Default")
      (node (ref "U1") (pin "D20") (pinfunction "PD7_D20") (pintype "passive+no_connect"))
    )
    (net (code "194") (name "unconnected-(U1A-PD8-PadC16)") (class "Default")
      (node (ref "U1") (pin "C16") (pinfunction "PD8_C16") (pintype "passive+no_connect"))
    )
    (net (code "195") (name "unconnected-(U1A-PD9-PadC15)") (class "Default")
      (node (ref "U1") (pin "C15") (pinfunction "PD9_C15") (pintype "passive+no_connect"))
    )
    (net (code "196") (name "unconnected-(U1A-PD10-PadC17)") (class "Default")
      (node (ref "U1") (pin "C17") (pinfunction "PD10_C17") (pintype "passive+no_connect"))
    )
    (net (code "197") (name "unconnected-(U1A-PD11-PadA15)") (class "Default")
      (node (ref "U1") (pin "A15") (pinfunction "PD11_A15") (pintype "passive+no_connect"))
    )
    (net (code "198") (name "unconnected-(U1B-PF6-PadAC7)") (class "Default")
      (node (ref "U1") (pin "AC7") (pinfunction "PF6_AC7") (pintype "passive+no_connect"))
    )
    (net (code "199") (name "unconnected-(U1B-PF8-PadAE10)") (class "Default")
      (node (ref "U1") (pin "AE10") (pinfunction "PF8_AE10") (pintype "passive+no_connect"))
    )
    (net (code "200") (name "unconnected-(U1B-PF9-PadAE8)") (class "Default")
      (node (ref "U1") (pin "AE8") (pinfunction "PF9_AE8") (pintype "passive+no_connect"))
    )
    (net (code "201") (name "unconnected-(U1B-PG0-PadAF7)") (class "Default")
      (node (ref "U1") (pin "AF7") (pinfunction "PG0_AF7") (pintype "passive+no_connect"))
    )
    (net (code "202") (name "unconnected-(U1B-PG3-PadAA7)") (class "Default")
      (node (ref "U1") (pin "AA7") (pinfunction "PG3_AA7") (pintype "passive+no_connect"))
    )
    (net (code "203") (name "unconnected-(U1B-PG12-PadN3)") (class "Default")
      (node (ref "U1") (pin "N3") (pinfunction "PG12_N3") (pintype "passive+no_connect"))
    )
    (net (code "204") (name "unconnected-(U1C-PI9-PadU1)") (class "Default")
      (node (ref "U1") (pin "U1") (pinfunction "PI9_U1") (pintype "passive+no_connect"))
    )
    (net (code "205") (name "unconnected-(U1C-PI10-PadD16)") (class "Default")
      (node (ref "U1") (pin "D16") (pinfunction "PI10_D16") (pintype "passive+no_connect"))
    )
  )
)
